# Converter_3V3-0V9_V1.net
KiCad netlist of a schematic drawn in Altium Designer
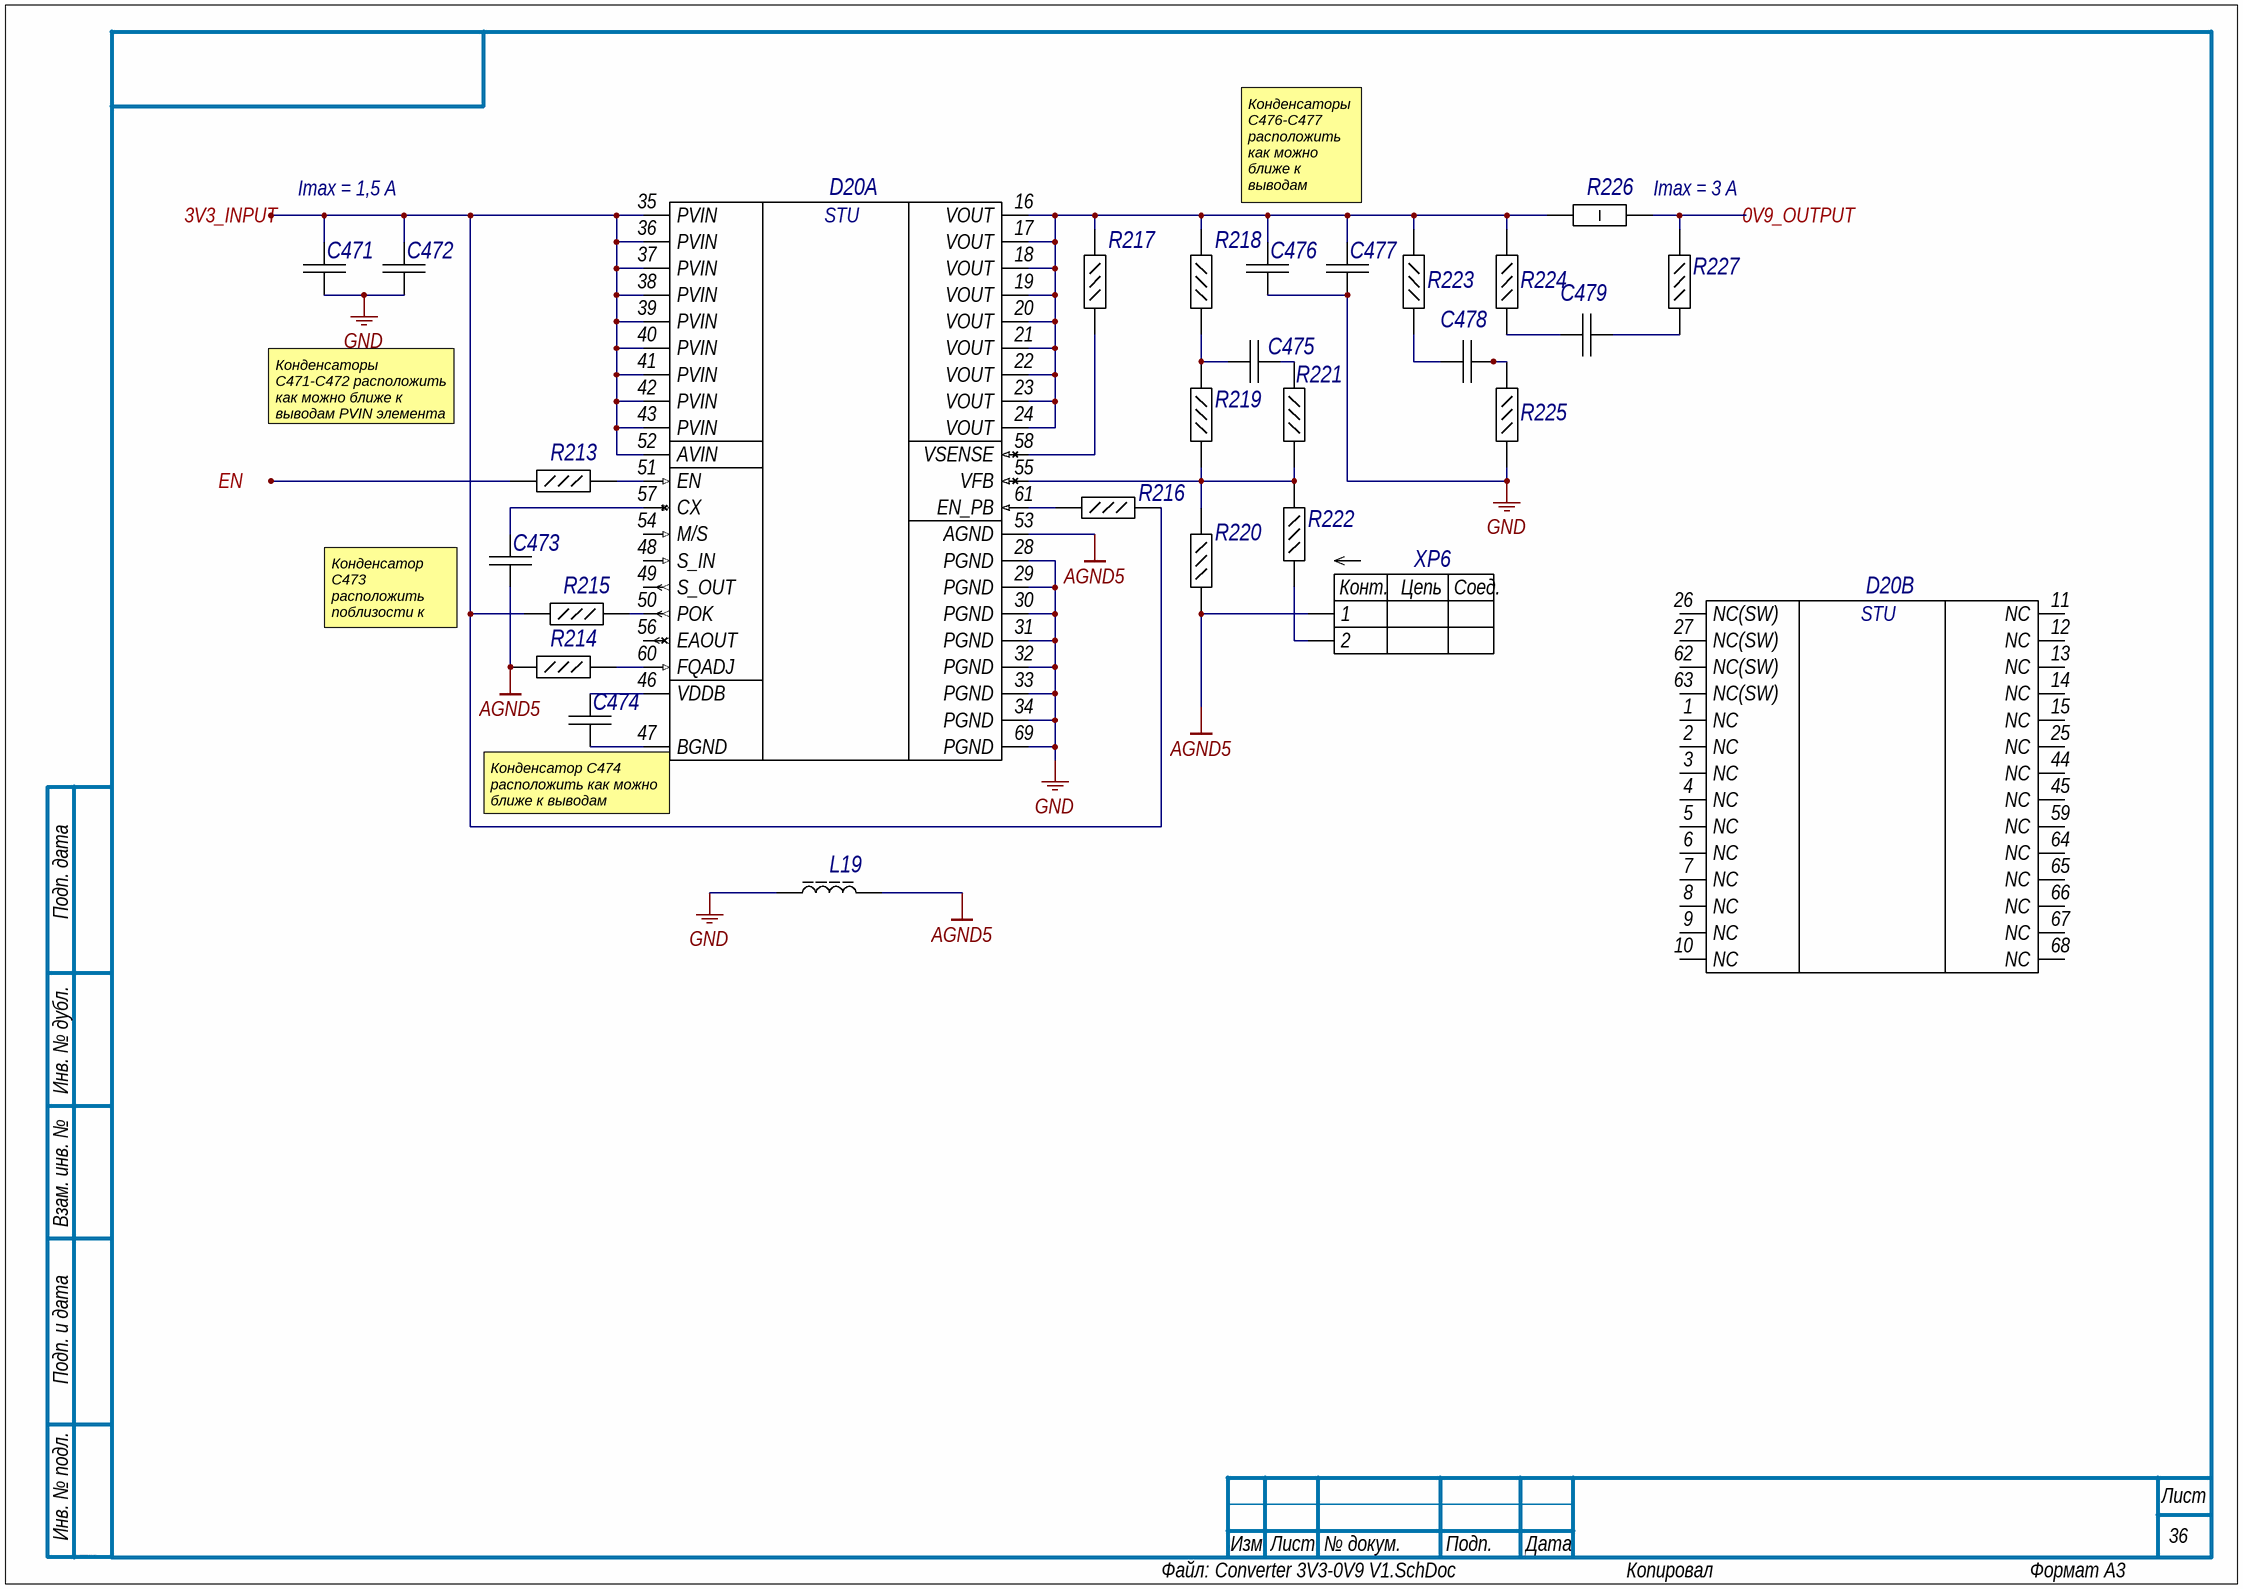
[diagram p0: Converter 3V3-0V9 V1.SchDoc]

(export (version "E")
  (design (tool "Eeschema 10.0.6"))
  (components
    (comp (ref "C471")
      (value "GRM31CR61E226KE15L")
      (footprint "CAPC3216X180X55ML20T25")
      (description "Chip Capacitor, 22 uF, +/- 10%, 25 V, -55 to 85 degC, 1206 (3216 Metric), RoHS, Tape and Reel")
      (fields (field (name "TOLERANCE") "10%"))
      (libsource (lib "MiniPC DB") (part "CAP_NP"))
    )
    (comp (ref "C472")
      (value "GRM31CR61E226KE15L")
      (footprint "CAPC3216X180X55ML20T25")
      (description "Chip Capacitor, 22 uF, +/- 10%, 25 V, -55 to 85 degC, 1206 (3216 Metric), RoHS, Tape and Reel")
      (fields (field (name "TOLERANCE") "10%"))
      (libsource (lib "MiniPC DB") (part "CAP_NP"))
    )
    (comp (ref "C473")
      (value "VJ0402Y153JXQPW1BC")
      (footprint "CAPC1005X55X23ML05T8")
      (description "Chip Capacitor, 15 nF, +/- 5%, 10 V, -55 to 125 degC, 0402 (1005 Metric), RoHS, Tape and Reel")
      (fields (field (name "TOLERANCE") "5%"))
      (libsource (lib "MiniPC DB") (part "CAP_NP"))
    )
    (comp (ref "C474")
      (value "GRM155R61A224KE19D")
      (footprint "CAPC1005X55X25NL05T10")
      (description "Chip Capacitor, 220 nF, +/- 10%, 10 V, -55 to 85 degC, 0402 (1005 Metric), RoHS, Tape and Reel")
      (fields (field (name "TOLERANCE") "10%") (field (name "MANUFACTURER") "Basic Passives"))
      (libsource (lib "MiniPC DB") (part "CAP_NP"))
    )
    (comp (ref "C475")
      (value "C1005C0G1H220J050BA")
      (footprint "CAPC1005X55X10LL05")
      (description "Chip Capacitor, 22 pF, +/- 5%, 50 V, -55 to 125 degC, 0402 (1005 Metric), RoHS, Tape and Reel")
      (fields (field (name "TOLERANCE") "5%"))
      (libsource (lib "MiniPC DB") (part "CAP_NP"))
    )
    (comp (ref "C476")
      (value "C3216X5R1A476M160AB")
      (footprint "CAPC3216X180X20ML20")
      (description "Chip Capacitor, 47 uF, +/- 20%, 10 V, -55 to 85 degC, 1206 (3216 Metric), RoHS, Tape and Reel")
      (fields (field (name "TOLERANCE") "20%"))
      (libsource (lib "MiniPC DB") (part "CAP_NP"))
    )
    (comp (ref "C477")
      (value "C3216X5R1A476M160AB")
      (footprint "CAPC3216X180X20ML20")
      (description "Chip Capacitor, 47 uF, +/- 20%, 10 V, -55 to 85 degC, 1206 (3216 Metric), RoHS, Tape and Reel")
      (fields (field (name "TOLERANCE") "20%"))
      (libsource (lib "MiniPC DB") (part "CAP_NP"))
    )
    (comp (ref "C478")
      (value "GRM155R61A224KE19D")
      (footprint "CAPC1005X55X25NL05T10")
      (description "Chip Capacitor, 220 nF, +/- 10%, 10 V, -55 to 85 degC, 0402 (1005 Metric), RoHS, Tape and Reel")
      (fields (field (name "TOLERANCE") "10%") (field (name "MANUFACTURER") "Basic Passives"))
      (libsource (lib "MiniPC DB") (part "CAP_NP"))
    )
    (comp (ref "C479")
      (value "CGB2A1X5R1E105K033BC")
      (footprint "CAPC1005X33X10LL5")
      (description "Chip Capacitor, 1 uF, +/- 10%, 25 V, -55 to 85 degC, 0402 (1005 Metric), RoHS, Tape and Reel")
      (fields (field (name "TOLERANCE") "10%"))
      (libsource (lib "MiniPC DB") (part "CAP_NP"))
    )
    (comp (ref "D20")
      (value "EN6360QI")
      (footprint "ALTR-QFN-68_A-305_V")
      (libsource (lib "MiniPC DB") (part "EN6360QI"))
    )
    (comp (ref "L19")
      (value "742792609")
      (footprint "SMD-0603")
      (description "SMD EMI Suppression Ferrite Bead WE-CBF, Z = 30 Ohm")
      (libsource (lib "MiniPC DB") (part "Choke"))
    )
    (comp (ref "R213")
      (value "NRC04F49R9TRF")
      (footprint "RESC1005X35X25NL8T10")
      (description "Chip Resistor, 49.9 Ohm, +/- 1%, 0.06 W, -55 to 155 degC, 0402 (1005 Metric), RoHS, Tape and Reel")
      (fields (field (name "TOLERANCE") "1%"))
      (libsource (lib "") (part "RES-0.05_1"))
    )
    (comp (ref "R214")
      (value "CRCW04023K57FKED")
      (footprint "RESC1005X40X25LL05T05")
      (description "Chip Resistor, 3.57 KOhm, +/- 1%, 63 mW, -55 to 155 degC, 0402 (1005 Metric), RoHS, Tape and Reel")
      (fields (field (name "TOLERANCE") "1%"))
      (libsource (lib "") (part "RES-0.05_1"))
    )
    (comp (ref "R215")
      (value "ERJ-2RKF1003X")
      (footprint "RESC1005X40X25LL05T05")
      (description "Chip Resistor, 100 KOhm, +/- 1%, 100 mW, -55 to 155 degC, 0402 (1005 Metric), RoHS, Tape and Reel")
      (fields (field (name "TOLERANCE") "1%") (field (name "MANUFACTURER") "Basic Passives"))
      (libsource (lib "") (part "RES-0.05_1"))
    )
    (comp (ref "R216")
      (value "ERJ-2RKF1002X")
      (footprint "RESC1005X40X25LL05T05")
      (description "Chip Resistor, 10 KOhm, +/- 1%, 100 mW, -55 to 155 degC, 0402 (1005 Metric), RoHS, Tape and Reel")
      (fields (field (name "TOLERANCE") "1%") (field (name "MANUFACTURER") "Basic Passives"))
      (libsource (lib "") (part "RES-0.05_1"))
    )
    (comp (ref "R217")
      (value "ERJ-2GE0R00X")
      (footprint "RESC1005X40X25LL05T05")
      (description "Chip Resistor, 0 mOhm, +/- 5%, 100 mW, -55 to 155 degC, 0402 (1005 Metric), RoHS, Tape and Reel")
      (fields (field (name "TOLERANCE") "5%") (field (name "MANUFACTURER") "Basic Passives"))
      (libsource (lib "") (part "RES-0.05_2"))
    )
    (comp (ref "R218")
      (value "ERJ-2GE0R00X")
      (footprint "RESC1005X40X25LL05T05")
      (description "Chip Resistor, 0 mOhm, +/- 5%, 100 mW, -55 to 155 degC, 0402 (1005 Metric), RoHS, Tape and Reel")
      (fields (field (name "TOLERANCE") "5%") (field (name "MANUFACTURER") "Basic Passives"))
      (libsource (lib "MiniPC DB") (part "RES-0.05"))
    )
    (comp (ref "R219")
      (value "CRCW0402160KFKED")
      (footprint "RESC1005X40X25LL05T05")
      (description "Chip Resistor, 160 KOhm, +/- 1%, 63 mW, -55 to 155 degC, 0402 (1005 Metric), RoHS, Tape and Reel")
      (fields (field (name "TOLERANCE") "1%") (field (name "MANUFACTURER") "Basic Passives"))
      (libsource (lib "MiniPC DB") (part "RES-0.05"))
    )
    (comp (ref "R220")
      (value "ERJ-2RKF3243X")
      (footprint "RESC1005X40X25LL05T05")
      (description "Chip Resistor, 324 KOhm, +/- 1%, 100 mW, -55 to 155 degC, 0402 (1005 Metric), RoHS, Tape and Reel")
      (fields (field (name "TOLERANCE") "1%") (field (name "MANUFACTURER") "Basic Passives"))
      (libsource (lib "") (part "RES-0.05_2"))
    )
    (comp (ref "R221")
      (value "ERJ-2RKF1502X")
      (footprint "RESC1005X40X25LL05T05")
      (description "Chip Resistor, 15 KOhm, +/- 1%, 100 mW, -55 to 155 degC, 0402 (1005 Metric), RoHS, Tape and Reel")
      (fields (field (name "TOLERANCE") "1%") (field (name "MANUFACTURER") "Basic Passives"))
      (libsource (lib "MiniPC DB") (part "RES-0.05"))
    )
    (comp (ref "R222")
      (value "CRCW04021M78FKED")
      (footprint "RESC1005X40X25LL05T05")
      (description "Chip Resistor, 1.78 MOhm, +/- 1%, 63 mW, -55 to 155 degC, 0402 (1005 Metric), RoHS, Tape and Reel")
      (fields (field (name "TOLERANCE") "1%") (field (name "MANUFACTURER") "Basic Passives"))
      (libsource (lib "") (part "RES-0.05_2"))
    )
    (comp (ref "R223")
      (value "ERJ-2RKF1000X")
      (footprint "RESC1005X40X25LL05T05")
      (description "Chip Resistor, 100 Ohm, +/- 1%, 100 mW, -55 to 155 degC, 0402 (1005 Metric), RoHS, Tape and Reel")
      (fields (field (name "TOLERANCE") "1%") (field (name "MANUFACTURER") "Basic Passives"))
      (libsource (lib "MiniPC DB") (part "RES-0.05"))
    )
    (comp (ref "R224")
      (value "ERJ-2RKF1002X")
      (footprint "RESC1005X40X25LL05T05")
      (description "Chip Resistor, 10 KOhm, +/- 1%, 100 mW, -55 to 155 degC, 0402 (1005 Metric), RoHS, Tape and Reel")
      (fields (field (name "TOLERANCE") "1%") (field (name "MANUFACTURER") "Basic Passives"))
      (libsource (lib "") (part "RES-0.05_2"))
    )
    (comp (ref "R225")
      (value "ERJ-2RKF1000X")
      (footprint "RESC1005X40X25LL05T05")
      (description "Chip Resistor, 100 Ohm, +/- 1%, 100 mW, -55 to 155 degC, 0402 (1005 Metric), RoHS, Tape and Reel")
      (fields (field (name "TOLERANCE") "1%") (field (name "MANUFACTURER") "Basic Passives"))
      (libsource (lib "") (part "RES-0.05_2"))
    )
    (comp (ref "R226")
      (value "WSLP12061L000FEA")
      (footprint "RESC3216X89X104LL25T25")
      (description "Chip Resistor, 0.001 Ohm, +/- 1%, 1 W, -65 to 170 degC, 1206 (3216 Metric), RoHS, Tape and Reel")
      (fields (field (name "TOLERANCE") "1%"))
      (libsource (lib "MiniPC DB") (part "RES-1"))
    )
    (comp (ref "R227")
      (value "ERJ-2RKF1002X")
      (footprint "RESC1005X40X25LL05T05")
      (description "Chip Resistor, 10 KOhm, +/- 1%, 100 mW, -55 to 155 degC, 0402 (1005 Metric), RoHS, Tape and Reel")
      (fields (field (name "TOLERANCE") "1%") (field (name "MANUFACTURER") "Basic Passives"))
      (libsource (lib "") (part "RES-0.05_2"))
    )
    (comp (ref "XP6")
      (value "613 002 111 21")
      (footprint "WE-61300211121_V")
      (fields (field (name "MANUFACTURER") "Wuerth Elektronik"))
      (libsource (lib "MiniPC DB") (part "VILKA_2K"))
    )
  )
  (nets
    (net (code "1") (name "/0V9_OUTPUT") (class "Default")
      (node (ref "R226") (pin "1") (pinfunction "1_1") (pintype "passive"))
      (node (ref "R227") (pin "2") (pinfunction "2_2") (pintype "passive"))
    )
    (net (code "2") (name "/3V3_INPUT") (class "Default")
      (node (ref "C471") (pin "2") (pinfunction "2_2") (pintype "passive"))
      (node (ref "C472") (pin "2") (pinfunction "2_2") (pintype "passive"))
      (node (ref "D20") (pin "35") (pinfunction "PVIN_35") (pintype "power_in"))
      (node (ref "D20") (pin "36") (pinfunction "PVIN_36") (pintype "power_in"))
      (node (ref "D20") (pin "37") (pinfunction "PVIN_37") (pintype "power_in"))
      (node (ref "D20") (pin "38") (pinfunction "PVIN_38") (pintype "power_in"))
      (node (ref "D20") (pin "39") (pinfunction "PVIN_39") (pintype "power_in"))
      (node (ref "D20") (pin "40") (pinfunction "PVIN_40") (pintype "power_in"))
      (node (ref "D20") (pin "41") (pinfunction "PVIN_41") (pintype "power_in"))
      (node (ref "D20") (pin "42") (pinfunction "PVIN_42") (pintype "power_in"))
      (node (ref "D20") (pin "43") (pinfunction "PVIN_43") (pintype "power_in"))
      (node (ref "D20") (pin "52") (pinfunction "AVIN_52") (pintype "power_in"))
      (node (ref "R215") (pin "2") (pinfunction "2_2") (pintype "passive"))
      (node (ref "R216") (pin "1") (pinfunction "1_1") (pintype "passive"))
    )
    (net (code "3") (name "/EN") (class "Default")
      (node (ref "R213") (pin "2") (pinfunction "2_2") (pintype "passive"))
    )
    (net (code "4") (name "AGND5") (class "Default")
      (node (ref "C473") (pin "1") (pinfunction "1_1") (pintype "passive"))
      (node (ref "D20") (pin "53") (pinfunction "AGND_53") (pintype "power_in"))
      (node (ref "L19") (pin "2") (pinfunction "2_2") (pintype "passive"))
      (node (ref "R214") (pin "2") (pinfunction "2_2") (pintype "passive"))
      (node (ref "R220") (pin "1") (pinfunction "1_1") (pintype "passive"))
      (node (ref "XP6") (pin "1") (pinfunction "1_1") (pintype "passive"))
    )
    (net (code "5") (name "GND") (class "Default")
      (node (ref "C471") (pin "1") (pinfunction "1_1") (pintype "passive"))
      (node (ref "C472") (pin "1") (pinfunction "1_1") (pintype "passive"))
      (node (ref "C476") (pin "1") (pinfunction "1_1") (pintype "passive"))
      (node (ref "C477") (pin "1") (pinfunction "1_1") (pintype "passive"))
      (node (ref "D20") (pin "28") (pinfunction "PGND_28") (pintype "power_in"))
      (node (ref "D20") (pin "29") (pinfunction "PGND_29") (pintype "power_in"))
      (node (ref "D20") (pin "30") (pinfunction "PGND_30") (pintype "power_in"))
      (node (ref "D20") (pin "31") (pinfunction "PGND_31") (pintype "power_in"))
      (node (ref "D20") (pin "32") (pinfunction "PGND_32") (pintype "power_in"))
      (node (ref "D20") (pin "33") (pinfunction "PGND_33") (pintype "power_in"))
      (node (ref "D20") (pin "34") (pinfunction "PGND_34") (pintype "power_in"))
      (node (ref "D20") (pin "69") (pinfunction "PGND_69") (pintype "power_in"))
      (node (ref "L19") (pin "1") (pinfunction "1_1") (pintype "passive"))
      (node (ref "R225") (pin "1") (pinfunction "1_1") (pintype "passive"))
    )
    (net (code "6") (name "Net-(C475-Pad1)") (class "Default")
      (node (ref "C475") (pin "1") (pinfunction "1_1") (pintype "passive"))
      (node (ref "R218") (pin "2") (pinfunction "2_2") (pintype "passive"))
      (node (ref "R219") (pin "1") (pinfunction "1_1") (pintype "passive"))
    )
    (net (code "7") (name "Net-(C475-Pad2)") (class "Default")
      (node (ref "C475") (pin "2") (pinfunction "2_2") (pintype "passive"))
      (node (ref "R221") (pin "1") (pinfunction "1_1") (pintype "passive"))
    )
    (net (code "8") (name "Net-(C476-Pad2)") (class "Default")
      (node (ref "C476") (pin "2") (pinfunction "2_2") (pintype "passive"))
      (node (ref "C477") (pin "2") (pinfunction "2_2") (pintype "passive"))
      (node (ref "D20") (pin "16") (pinfunction "VOUT_16") (pintype "power_in"))
      (node (ref "D20") (pin "17") (pinfunction "VOUT_17") (pintype "power_in"))
      (node (ref "D20") (pin "18") (pinfunction "VOUT_18") (pintype "power_in"))
      (node (ref "D20") (pin "19") (pinfunction "VOUT_19") (pintype "power_in"))
      (node (ref "D20") (pin "20") (pinfunction "VOUT_20") (pintype "power_in"))
      (node (ref "D20") (pin "21") (pinfunction "VOUT_21") (pintype "power_in"))
      (node (ref "D20") (pin "22") (pinfunction "VOUT_22") (pintype "power_in"))
      (node (ref "D20") (pin "23") (pinfunction "VOUT_23") (pintype "power_in"))
      (node (ref "D20") (pin "24") (pinfunction "VOUT_24") (pintype "power_in"))
      (node (ref "R217") (pin "2") (pinfunction "2_2") (pintype "passive"))
      (node (ref "R218") (pin "1") (pinfunction "1_1") (pintype "passive"))
      (node (ref "R223") (pin "1") (pinfunction "1_1") (pintype "passive"))
      (node (ref "R224") (pin "2") (pinfunction "2_2") (pintype "passive"))
      (node (ref "R226") (pin "2") (pinfunction "2_2") (pintype "passive"))
    )
    (net (code "9") (name "Net-(C478-Pad1)") (class "Default")
      (node (ref "C478") (pin "1") (pinfunction "1_1") (pintype "passive"))
      (node (ref "R223") (pin "2") (pinfunction "2_2") (pintype "passive"))
    )
    (net (code "10") (name "Net-(C478-Pad2)") (class "Default")
      (node (ref "C478") (pin "2") (pinfunction "2_2") (pintype "passive"))
      (node (ref "R225") (pin "2") (pinfunction "2_2") (pintype "passive"))
    )
    (net (code "11") (name "Net-(C479-Pad1)") (class "Default")
      (node (ref "C479") (pin "1") (pinfunction "1_1") (pintype "passive"))
      (node (ref "R227") (pin "1") (pinfunction "1_1") (pintype "passive"))
    )
    (net (code "12") (name "Net-(C479-Pad2)") (class "Default")
      (node (ref "C479") (pin "2") (pinfunction "2_2") (pintype "passive"))
      (node (ref "R224") (pin "1") (pinfunction "1_1") (pintype "passive"))
    )
    (net (code "13") (name "Net-(D20A-BGND)") (class "Default")
      (node (ref "C474") (pin "1") (pinfunction "1_1") (pintype "passive"))
      (node (ref "D20") (pin "47") (pinfunction "BGND_47") (pintype "power_in"))
    )
    (net (code "14") (name "Net-(D20A-CX)") (class "Default")
      (node (ref "C473") (pin "2") (pinfunction "2_2") (pintype "passive"))
      (node (ref "D20") (pin "57") (pinfunction "CX_57") (pintype "input"))
    )
    (net (code "15") (name "Net-(D20A-EN)") (class "Default")
      (node (ref "D20") (pin "51") (pinfunction "EN_51") (pintype "input"))
      (node (ref "R213") (pin "1") (pinfunction "1_1") (pintype "passive"))
    )
    (net (code "16") (name "Net-(D20A-EN_PB)") (class "Default")
      (node (ref "D20") (pin "61") (pinfunction "EN_PB_61") (pintype "input"))
      (node (ref "R216") (pin "2") (pinfunction "2_2") (pintype "passive"))
    )
    (net (code "17") (name "Net-(D20A-FQADJ)") (class "Default")
      (node (ref "D20") (pin "60") (pinfunction "FQADJ_60") (pintype "input"))
      (node (ref "R214") (pin "1") (pinfunction "1_1") (pintype "passive"))
    )
    (net (code "18") (name "Net-(D20A-POK)") (class "Default")
      (node (ref "D20") (pin "50") (pinfunction "POK_50") (pintype "output"))
      (node (ref "R215") (pin "1") (pinfunction "1_1") (pintype "passive"))
    )
    (net (code "19") (name "Net-(D20A-VDDB)") (class "Default")
      (node (ref "C474") (pin "2") (pinfunction "2_2") (pintype "passive"))
      (node (ref "D20") (pin "46") (pinfunction "VDDB_46") (pintype "power_in"))
    )
    (net (code "20") (name "Net-(D20A-VFB)") (class "Default")
      (node (ref "D20") (pin "55") (pinfunction "VFB_55") (pintype "input"))
      (node (ref "R219") (pin "2") (pinfunction "2_2") (pintype "passive"))
      (node (ref "R220") (pin "2") (pinfunction "2_2") (pintype "passive"))
      (node (ref "R221") (pin "2") (pinfunction "2_2") (pintype "passive"))
      (node (ref "R222") (pin "2") (pinfunction "2_2") (pintype "passive"))
    )
    (net (code "21") (name "Net-(D20A-VSENSE)") (class "Default")
      (node (ref "D20") (pin "58") (pinfunction "VSENSE_58") (pintype "input"))
      (node (ref "R217") (pin "1") (pinfunction "1_1") (pintype "passive"))
    )
    (net (code "22") (name "Net-(R222-Pad1)") (class "Default")
      (node (ref "R222") (pin "1") (pinfunction "1_1") (pintype "passive"))
      (node (ref "XP6") (pin "2") (pinfunction "2_2") (pintype "passive"))
    )
    (net (code "23") (name "unconnected-(D20A-EAOUT-Pad56)") (class "Default")
      (node (ref "D20") (pin "56") (pinfunction "EAOUT_56") (pintype "output"))
    )
    (net (code "24") (name "unconnected-(D20A-M{slash}S-Pad54)") (class "Default")
      (node (ref "D20") (pin "54") (pinfunction "M/S_54") (pintype "input"))
    )
    (net (code "25") (name "unconnected-(D20A-S_IN-Pad48)") (class "Default")
      (node (ref "D20") (pin "48") (pinfunction "S_IN_48") (pintype "input"))
    )
    (net (code "26") (name "unconnected-(D20A-S_OUT-Pad49)") (class "Default")
      (node (ref "D20") (pin "49") (pinfunction "S_OUT_49") (pintype "output"))
    )
    (net (code "27") (name "unconnected-(D20B-NC(SW)-Pad26)") (class "Default")
      (node (ref "D20") (pin "26") (pinfunction "NC(SW)_26") (pintype "passive"))
    )
    (net (code "28") (name "unconnected-(D20B-NC(SW)-Pad27)") (class "Default")
      (node (ref "D20") (pin "27") (pinfunction "NC(SW)_27") (pintype "passive"))
    )
    (net (code "29") (name "unconnected-(D20B-NC(SW)-Pad62)") (class "Default")
      (node (ref "D20") (pin "62") (pinfunction "NC(SW)_62") (pintype "passive"))
    )
    (net (code "30") (name "unconnected-(D20B-NC(SW)-Pad63)") (class "Default")
      (node (ref "D20") (pin "63") (pinfunction "NC(SW)_63") (pintype "passive"))
    )
    (net (code "31") (name "unconnected-(D20B-NC-Pad1)") (class "Default")
      (node (ref "D20") (pin "1") (pinfunction "NC_1") (pintype "passive"))
    )
    (net (code "32") (name "unconnected-(D20B-NC-Pad2)") (class "Default")
      (node (ref "D20") (pin "2") (pinfunction "NC_2") (pintype "passive"))
    )
    (net (code "33") (name "unconnected-(D20B-NC-Pad3)") (class "Default")
      (node (ref "D20") (pin "3") (pinfunction "NC_3") (pintype "passive"))
    )
    (net (code "34") (name "unconnected-(D20B-NC-Pad4)") (class "Default")
      (node (ref "D20") (pin "4") (pinfunction "NC_4") (pintype "passive"))
    )
    (net (code "35") (name "unconnected-(D20B-NC-Pad5)") (class "Default")
      (node (ref "D20") (pin "5") (pinfunction "NC_5") (pintype "passive"))
    )
    (net (code "36") (name "unconnected-(D20B-NC-Pad6)") (class "Default")
      (node (ref "D20") (pin "6") (pinfunction "NC_6") (pintype "passive"))
    )
    (net (code "37") (name "unconnected-(D20B-NC-Pad7)") (class "Default")
      (node (ref "D20") (pin "7") (pinfunction "NC_7") (pintype "passive"))
    )
    (net (code "38") (name "unconnected-(D20B-NC-Pad8)") (class "Default")
      (node (ref "D20") (pin "8") (pinfunction "NC_8") (pintype "passive"))
    )
    (net (code "39") (name "unconnected-(D20B-NC-Pad9)") (class "Default")
      (node (ref "D20") (pin "9") (pinfunction "NC_9") (pintype "passive"))
    )
    (net (code "40") (name "unconnected-(D20B-NC-Pad10)") (class "Default")
      (node (ref "D20") (pin "10") (pinfunction "NC_10") (pintype "passive"))
    )
    (net (code "41") (name "unconnected-(D20B-NC-Pad11)") (class "Default")
      (node (ref "D20") (pin "11") (pinfunction "NC_11") (pintype "passive"))
    )
    (net (code "42") (name "unconnected-(D20B-NC-Pad12)") (class "Default")
      (node (ref "D20") (pin "12") (pinfunction "NC_12") (pintype "passive"))
    )
    (net (code "43") (name "unconnected-(D20B-NC-Pad13)") (class "Default")
      (node (ref "D20") (pin "13") (pinfunction "NC_13") (pintype "passive"))
    )
    (net (code "44") (name "unconnected-(D20B-NC-Pad14)") (class "Default")
      (node (ref "D20") (pin "14") (pinfunction "NC_14") (pintype "passive"))
    )
    (net (code "45") (name "unconnected-(D20B-NC-Pad15)") (class "Default")
      (node (ref "D20") (pin "15") (pinfunction "NC_15") (pintype "passive"))
    )
    (net (code "46") (name "unconnected-(D20B-NC-Pad25)") (class "Default")
      (node (ref "D20") (pin "25") (pinfunction "NC_25") (pintype "passive"))
    )
    (net (code "47") (name "unconnected-(D20B-NC-Pad44)") (class "Default")
      (node (ref "D20") (pin "44") (pinfunction "NC_44") (pintype "passive"))
    )
    (net (code "48") (name "unconnected-(D20B-NC-Pad45)") (class "Default")
      (node (ref "D20") (pin "45") (pinfunction "NC_45") (pintype "passive"))
    )
    (net (code "49") (name "unconnected-(D20B-NC-Pad59)") (class "Default")
      (node (ref "D20") (pin "59") (pinfunction "NC_59") (pintype "passive"))
    )
    (net (code "50") (name "unconnected-(D20B-NC-Pad64)") (class "Default")
      (node (ref "D20") (pin "64") (pinfunction "NC_64") (pintype "passive"))
    )
    (net (code "51") (name "unconnected-(D20B-NC-Pad65)") (class "Default")
      (node (ref "D20") (pin "65") (pinfunction "NC_65") (pintype "passive"))
    )
    (net (code "52") (name "unconnected-(D20B-NC-Pad66)") (class "Default")
      (node (ref "D20") (pin "66") (pinfunction "NC_66") (pintype "passive"))
    )
    (net (code "53") (name "unconnected-(D20B-NC-Pad67)") (class "Default")
      (node (ref "D20") (pin "67") (pinfunction "NC_67") (pintype "passive"))
    )
    (net (code "54") (name "unconnected-(D20B-NC-Pad68)") (class "Default")
      (node (ref "D20") (pin "68") (pinfunction "NC_68") (pintype "passive"))
    )
  )
)
